# MCU_Power_Clock_Debug.net
KiCad netlist of a schematic drawn in Altium Designer
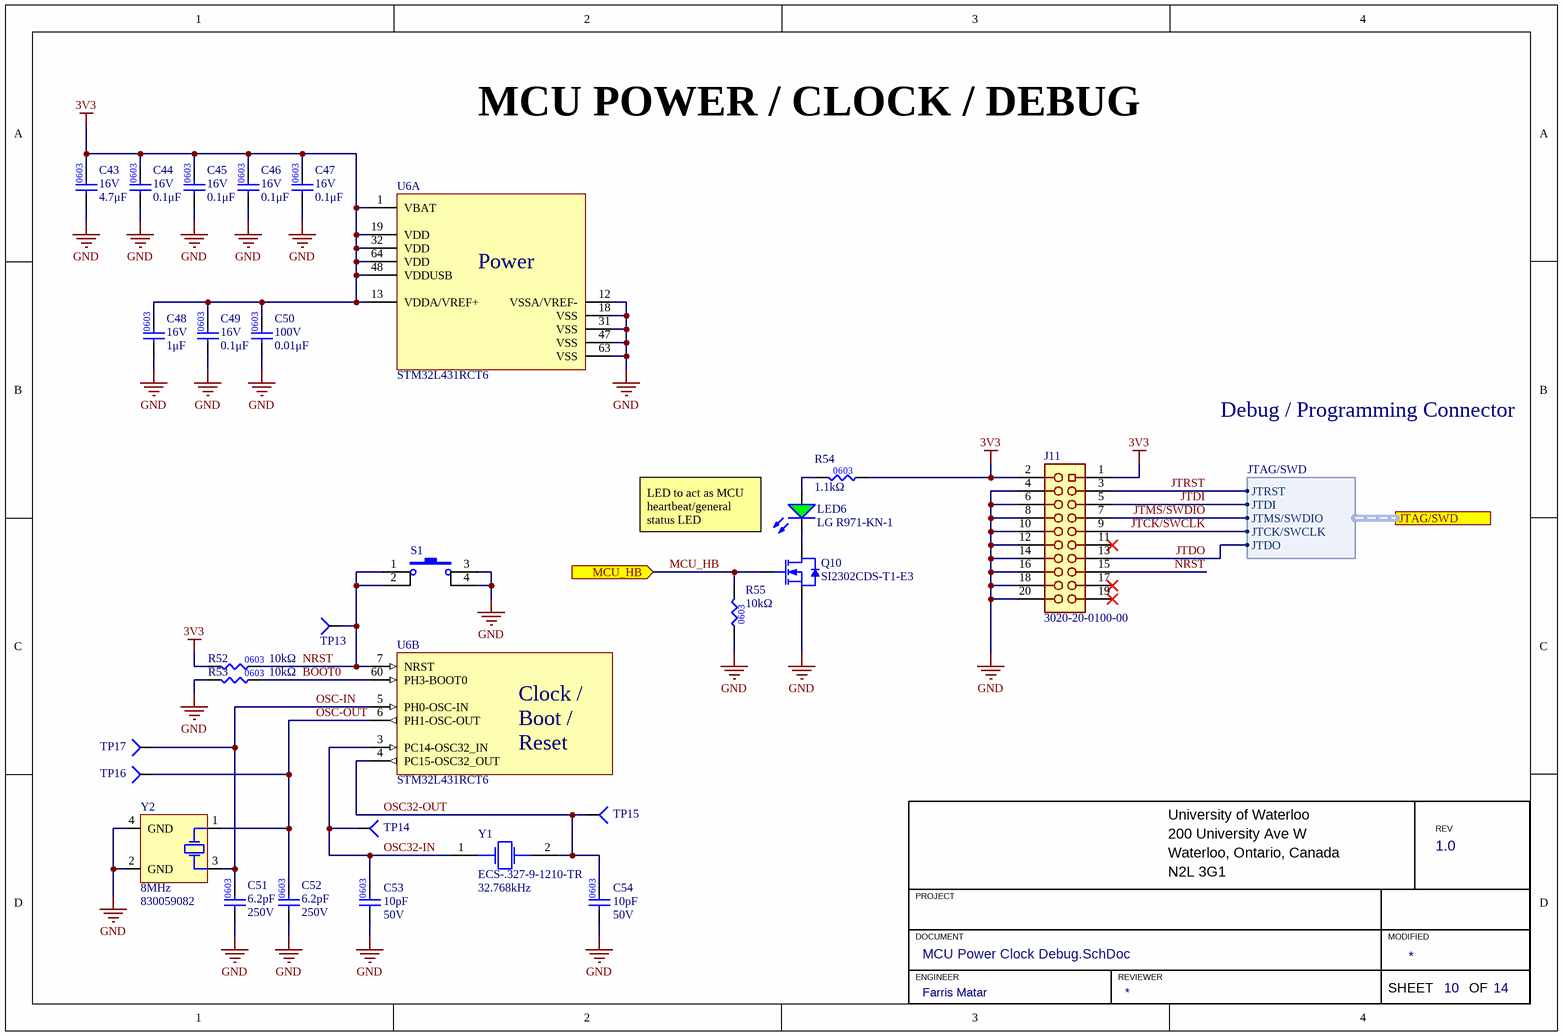
[diagram p0: MCU Power Clock Debug.SchDoc]

(export (version "E")
  (design (tool "Eeschema 10.0.6"))
  (components
    (comp (ref "C43")
      (value "4.7μF")
      (footprint "CAP0603")
      (description "CAP CER 4.7UF 16V X6S 0603")
      (fields (field (name "VOLTAGE RATING") "16V") (field (name "Comment") "CAP_4.7uF_16V_0603"))
      (libsource (lib "Personal_Schematic_Library_2022") (part "CAP_4.7uF_16V_0603"))
    )
    (comp (ref "C44")
      (value "0.1μF")
      (footprint "CAP0603")
      (description "CAP CER 0.1UF 16V X7R 0603")
      (fields (field (name "VOLTAGE RATING") "16V") (field (name "Comment") "CAP_0.1uF_16V_0603"))
      (libsource (lib "Personal_Schematic_Library_2022") (part "CAP_0.1uF_16V_0603"))
    )
    (comp (ref "C45")
      (value "0.1μF")
      (footprint "CAP0603")
      (description "CAP CER 0.1UF 16V X7R 0603")
      (fields (field (name "VOLTAGE RATING") "16V") (field (name "Comment") "CAP_0.1uF_16V_0603"))
      (libsource (lib "Personal_Schematic_Library_2022") (part "CAP_0.1uF_16V_0603"))
    )
    (comp (ref "C46")
      (value "0.1μF")
      (footprint "CAP0603")
      (description "CAP CER 0.1UF 16V X7R 0603")
      (fields (field (name "VOLTAGE RATING") "16V") (field (name "Comment") "CAP_0.1uF_16V_0603"))
      (libsource (lib "Personal_Schematic_Library_2022") (part "CAP_0.1uF_16V_0603"))
    )
    (comp (ref "C47")
      (value "0.1μF")
      (footprint "CAP0603")
      (description "CAP CER 0.1UF 16V X7R 0603")
      (fields (field (name "VOLTAGE RATING") "16V") (field (name "Comment") "CAP_0.1uF_16V_0603"))
      (libsource (lib "Personal_Schematic_Library_2022") (part "CAP_0.1uF_16V_0603"))
    )
    (comp (ref "C48")
      (value "1μF")
      (footprint "CAP0603")
      (description "CAP CER 1UF 16V X7R 0603")
      (fields (field (name "VOLTAGE RATING") "16V") (field (name "Comment") "CAP_1uF_16V_0603"))
      (libsource (lib "Personal_Schematic_Library_2022") (part "CAP_1uF_16V_0603"))
    )
    (comp (ref "C49")
      (value "0.1μF")
      (footprint "CAP0603")
      (description "CAP CER 0.1UF 16V X7R 0603")
      (fields (field (name "VOLTAGE RATING") "16V") (field (name "Comment") "CAP_0.1uF_16V_0603"))
      (libsource (lib "Personal_Schematic_Library_2022") (part "CAP_0.1uF_16V_0603"))
    )
    (comp (ref "C50")
      (value "0.01μF")
      (footprint "CAP0603")
      (description "CAP CER 0.01uF 100V X7R 0603")
      (fields (field (name "VOLTAGE RATING") "100V") (field (name "Comment") "CAP_0.01uF_100V_0603"))
      (libsource (lib "Personal_Schematic_Library_2022") (part "CAP_0.01uF_100V_0603"))
    )
    (comp (ref "C51")
      (value "6.2pF")
      (footprint "CAP0603")
      (description "HVCAP0603 COG 6.2PF .25PF 250V")
      (fields (field (name "VOLTAGE RATING") "250V") (field (name "Comment") "CAP_6.2pF_250V_0603"))
      (libsource (lib "Personal_Schematic_Library_2022") (part "CAP_6.2pF_250V_0603"))
    )
    (comp (ref "C52")
      (value "6.2pF")
      (footprint "CAP0603")
      (description "HVCAP0603 COG 6.2PF .25PF 250V")
      (fields (field (name "VOLTAGE RATING") "250V") (field (name "Comment") "CAP_6.2pF_250V_0603"))
      (libsource (lib "Personal_Schematic_Library_2022") (part "CAP_6.2pF_250V_0603"))
    )
    (comp (ref "C53")
      (value "10pF")
      (footprint "CAP0603")
      (description "CAP CER 10PF 50V X7R 0603")
      (fields (field (name "VOLTAGE RATING") "50V") (field (name "Comment") "CAP_10pF_50V_0603"))
      (libsource (lib "Personal_Schematic_Library_2022") (part "CAP_10pF_50V_0603"))
    )
    (comp (ref "C54")
      (value "10pF")
      (footprint "CAP0603")
      (description "CAP CER 10PF 50V X7R 0603")
      (fields (field (name "VOLTAGE RATING") "50V") (field (name "Comment") "CAP_10pF_50V_0603"))
      (libsource (lib "Personal_Schematic_Library_2022") (part "CAP_10pF_50V_0603"))
    )
    (comp (ref "J11")
      (value "3020-20-0100-00")
      (footprint "CNC_3020-20-0100-00")
      (description "CONN HEADER VERT 20POS 2.54MM")
      (libsource (lib "Personal_Schematic_Library_2022") (part "CON_10x2_HEADER"))
    )
    (comp (ref "LED6")
      (value "LED_GREEN")
      (footprint "LED_0805_GREEN")
      (description "LED GREEN DIFFUSED 0805 SMD")
      (fields (field (name "MANUFACTURER PART NUMBER 1") "LG R971-KN-1"))
      (libsource (lib "Personal_Schematic_Library_2022") (part "LED_GREEN"))
    )
    (comp (ref "Q10")
      (value "NMOS_20V_6A")
      (footprint "SOT23-3")
      (description "MOSFET N-CH 20V 2.6A SOT23-3")
      (fields (field (name "MANUFACTURER PART NUMBER 1") "SI2302CDS-T1-E3"))
      (libsource (lib "Personal_Schematic_Library_2022") (part "NMOS_20V_2.6A"))
    )
    (comp (ref "R52")
      (value "10kΩ")
      (footprint "RES0603")
      (description "RES 10K OHM 1% 1/8W 0603")
      (fields (field (name "Comment") "RES_10kΩ_0603_1%"))
      (libsource (lib "Personal_Schematic_Library_2022") (part "RES_10kΩ_0603_1%"))
    )
    (comp (ref "R53")
      (value "10kΩ")
      (footprint "RES0603")
      (description "RES 10K OHM 1% 1/8W 0603")
      (fields (field (name "Comment") "RES_10kΩ_0603_1%"))
      (libsource (lib "Personal_Schematic_Library_2022") (part "RES_10kΩ_0603_1%"))
    )
    (comp (ref "R54")
      (value "1.1kΩ")
      (footprint "RES0603")
      (description "RES 1.1K OHM 1% 1/10W 0603")
      (fields (field (name "Comment") "RES_1.1kΩ_0603_1%"))
      (libsource (lib "Personal_Schematic_Library_2022") (part "RES_1.1kΩ_0603_1%"))
    )
    (comp (ref "R55")
      (value "10kΩ")
      (footprint "RES0603")
      (description "RES 10K OHM 1% 1/8W 0603")
      (fields (field (name "Comment") "RES_10kΩ_0603_1%"))
      (libsource (lib "Personal_Schematic_Library_2022") (part "RES_10kΩ_0603_1%"))
    )
    (comp (ref "S1")
      (value "SW_SPST_NO_4.5x4.5")
      (footprint "SPST_PUSHBUTTON_TL3305AF260QG")
      (description "SWITCH TACTILE SPST-NO 50MA 12V")
      (libsource (lib "Personal_Schematic_Library_2022") (part "SW_SPST_NO_4.5x4.5"))
    )
    (comp (ref "TP13")
      (value "TESTPOINT_1MM_CIRCLE")
      (footprint "TESTPOINT_CIRCLE_1MM")
      (description "TESTPOINT 1MM CIRCLE")
      (libsource (lib "Personal_Schematic_Library_2022") (part "TESTPOINT_1MM_CIRCLE"))
    )
    (comp (ref "TP14")
      (value "TESTPOINT_1MM_CIRCLE")
      (footprint "TESTPOINT_CIRCLE_1MM")
      (description "TESTPOINT 1MM CIRCLE")
      (libsource (lib "Personal_Schematic_Library_2022") (part "TESTPOINT_1MM_CIRCLE"))
    )
    (comp (ref "TP15")
      (value "TESTPOINT_1MM_CIRCLE")
      (footprint "TESTPOINT_CIRCLE_1MM")
      (description "TESTPOINT 1MM CIRCLE")
      (libsource (lib "Personal_Schematic_Library_2022") (part "TESTPOINT_1MM_CIRCLE"))
    )
    (comp (ref "TP16")
      (value "TESTPOINT_1MM_CIRCLE")
      (footprint "TESTPOINT_CIRCLE_1MM")
      (description "TESTPOINT 1MM CIRCLE")
      (libsource (lib "Personal_Schematic_Library_2022") (part "TESTPOINT_1MM_CIRCLE"))
    )
    (comp (ref "TP17")
      (value "TESTPOINT_1MM_CIRCLE")
      (footprint "TESTPOINT_CIRCLE_1MM")
      (description "TESTPOINT 1MM CIRCLE")
      (libsource (lib "Personal_Schematic_Library_2022") (part "TESTPOINT_1MM_CIRCLE"))
    )
    (comp (ref "U6")
      (value "STM32L431RCT6")
      (footprint "STM_LQFP64")
      (description "IC MCU 32BIT 256KB FLASH 64LQFP")
      (libsource (lib "Personal_Schematic_Library_2022") (part "STM32L431RCT6"))
    )
    (comp (ref "Y1")
      (value "CRYSTAL_32.768KHZ")
      (footprint "OSC_ECS-327TR-2")
      (description "CRYSTAL 32.7680KHZ 9PF SMD")
      (fields
        (field (name "FREQUENCY") "32.768kHz")
        (field (name "MANUFACTURER PART NUMBER 1") "ECS-.327-9-1210-TR")
      )
      (libsource (lib "Personal_Schematic_Library_2022") (part "CRYSTAL_32.768KHZ"))
    )
    (comp (ref "Y2")
      (value "CRYSTAL_25MHZ")
      (footprint "XTAL_WURTH_830059082")
      (description "WE-XTAL QUARTZ CRYSTAL 8.0 MHZ;")
      (fields (field (name "FREQUENCY") "8MHz") (field (name "MANUFACTURER PART NUMBER 1") "830059082"))
      (libsource (lib "Personal_Schematic_Library_2022") (part "CRYSTAL_8MHZ_8PF"))
    )
  )
  (nets
    (net (code "2") (name "/BOOT0") (class "Default")
      (node (ref "R53") (pin "2") (pinfunction "2_2") (pintype "passive"))
      (node (ref "U6") (pin "60") (pinfunction "PH3-BOOT0_60") (pintype "input"))
    )
    (net (code "3") (name "/JTCK{slash}SWCLK") (class "Default")
      (node (ref "J11") (pin "9") (pinfunction "9_9") (pintype "passive"))
    )
    (net (code "4") (name "/JTDI") (class "Default")
      (node (ref "J11") (pin "5") (pinfunction "5_5") (pintype "passive"))
    )
    (net (code "5") (name "/JTDO") (class "Default")
      (node (ref "J11") (pin "13") (pinfunction "13_13") (pintype "passive"))
    )
    (net (code "6") (name "/JTMS{slash}SWDIO") (class "Default")
      (node (ref "J11") (pin "7") (pinfunction "7_7") (pintype "passive"))
    )
    (net (code "7") (name "/JTRST") (class "Default")
      (node (ref "J11") (pin "3") (pinfunction "3_3") (pintype "passive"))
    )
    (net (code "8") (name "/MCU_HB") (class "Default")
      (node (ref "Q10") (pin "1") (pinfunction "GATE_1") (pintype "passive"))
      (node (ref "R55") (pin "2") (pinfunction "2_2") (pintype "passive"))
    )
    (net (code "9") (name "/NRST") (class "Default")
      (node (ref "J11") (pin "15") (pinfunction "15_15") (pintype "passive"))
      (node (ref "R52") (pin "2") (pinfunction "2_2") (pintype "passive"))
      (node (ref "S1") (pin "1") (pinfunction "1_1") (pintype "passive"))
      (node (ref "S1") (pin "2") (pinfunction "2_2") (pintype "passive"))
      (node (ref "TP13") (pin "1") (pinfunction "=value_1") (pintype "passive"))
      (node (ref "U6") (pin "7") (pinfunction "NRST_7") (pintype "input"))
    )
    (net (code "10") (name "/OSC-IN") (class "Default")
      (node (ref "C51") (pin "2") (pinfunction "2_2") (pintype "passive"))
      (node (ref "TP17") (pin "1") (pinfunction "=value_1") (pintype "passive"))
      (node (ref "U6") (pin "5") (pinfunction "PH0-OSC-IN_5") (pintype "input"))
      (node (ref "Y2") (pin "3") (pinfunction "HOT_3") (pintype "passive"))
    )
    (net (code "11") (name "/OSC-OUT") (class "Default")
      (node (ref "C52") (pin "2") (pinfunction "2_2") (pintype "passive"))
      (node (ref "TP16") (pin "1") (pinfunction "=value_1") (pintype "passive"))
      (node (ref "U6") (pin "6") (pinfunction "PH1-OSC-OUT_6") (pintype "output"))
      (node (ref "Y2") (pin "1") (pinfunction "HOT_1") (pintype "passive"))
    )
    (net (code "12") (name "/OSC32-IN") (class "Default")
      (node (ref "C53") (pin "2") (pinfunction "2_2") (pintype "passive"))
      (node (ref "TP14") (pin "1") (pinfunction "=value_1") (pintype "passive"))
      (node (ref "U6") (pin "3") (pinfunction "PC14-OSC32_IN_3") (pintype "input"))
      (node (ref "Y1") (pin "1") (pinfunction "1_1") (pintype "passive"))
    )
    (net (code "13") (name "/OSC32-OUT") (class "Default")
      (node (ref "C54") (pin "2") (pinfunction "2_2") (pintype "passive"))
      (node (ref "TP15") (pin "1") (pinfunction "=value_1") (pintype "passive"))
      (node (ref "U6") (pin "4") (pinfunction "PC15-OSC32_OUT_4") (pintype "output"))
      (node (ref "Y1") (pin "2") (pinfunction "2_2") (pintype "passive"))
    )
    (net (code "15") (name "3V3") (class "Default")
      (node (ref "C43") (pin "2") (pinfunction "2_2") (pintype "passive"))
      (node (ref "C44") (pin "2") (pinfunction "2_2") (pintype "passive"))
      (node (ref "C45") (pin "2") (pinfunction "2_2") (pintype "passive"))
      (node (ref "C46") (pin "2") (pinfunction "2_2") (pintype "passive"))
      (node (ref "C47") (pin "2") (pinfunction "2_2") (pintype "passive"))
      (node (ref "C48") (pin "2") (pinfunction "2_2") (pintype "passive"))
      (node (ref "C49") (pin "2") (pinfunction "2_2") (pintype "passive"))
      (node (ref "C50") (pin "2") (pinfunction "2_2") (pintype "passive"))
      (node (ref "J11") (pin "1") (pinfunction "1_1") (pintype "passive"))
      (node (ref "J11") (pin "2") (pinfunction "2_2") (pintype "passive"))
      (node (ref "R52") (pin "1") (pinfunction "1_1") (pintype "passive"))
      (node (ref "R54") (pin "1") (pinfunction "1_1") (pintype "passive"))
      (node (ref "U6") (pin "1") (pinfunction "VBAT_1") (pintype "power_in"))
      (node (ref "U6") (pin "13") (pinfunction "VDDA/VREF+_13") (pintype "power_in"))
      (node (ref "U6") (pin "19") (pinfunction "VDD_19") (pintype "power_in"))
      (node (ref "U6") (pin "32") (pinfunction "VDD_32") (pintype "power_in"))
      (node (ref "U6") (pin "48") (pinfunction "VDDUSB_48") (pintype "power_in"))
      (node (ref "U6") (pin "64") (pinfunction "VDD_64") (pintype "power_in"))
    )
    (net (code "16") (name "GND") (class "Default")
      (node (ref "C43") (pin "1") (pinfunction "1_1") (pintype "passive"))
      (node (ref "C44") (pin "1") (pinfunction "1_1") (pintype "passive"))
      (node (ref "C45") (pin "1") (pinfunction "1_1") (pintype "passive"))
      (node (ref "C46") (pin "1") (pinfunction "1_1") (pintype "passive"))
      (node (ref "C47") (pin "1") (pinfunction "1_1") (pintype "passive"))
      (node (ref "C48") (pin "1") (pinfunction "1_1") (pintype "passive"))
      (node (ref "C49") (pin "1") (pinfunction "1_1") (pintype "passive"))
      (node (ref "C50") (pin "1") (pinfunction "1_1") (pintype "passive"))
      (node (ref "C51") (pin "1") (pinfunction "1_1") (pintype "passive"))
      (node (ref "C52") (pin "1") (pinfunction "1_1") (pintype "passive"))
      (node (ref "C53") (pin "1") (pinfunction "1_1") (pintype "passive"))
      (node (ref "C54") (pin "1") (pinfunction "1_1") (pintype "passive"))
      (node (ref "J11") (pin "10") (pinfunction "10_10") (pintype "passive"))
      (node (ref "J11") (pin "12") (pinfunction "12_12") (pintype "passive"))
      (node (ref "J11") (pin "14") (pinfunction "14_14") (pintype "passive"))
      (node (ref "J11") (pin "16") (pinfunction "16_16") (pintype "passive"))
      (node (ref "J11") (pin "18") (pinfunction "18_18") (pintype "passive"))
      (node (ref "J11") (pin "20") (pinfunction "20_20") (pintype "passive"))
      (node (ref "J11") (pin "4") (pinfunction "4_4") (pintype "passive"))
      (node (ref "J11") (pin "6") (pinfunction "6_6") (pintype "passive"))
      (node (ref "J11") (pin "8") (pinfunction "8_8") (pintype "passive"))
      (node (ref "Q10") (pin "2") (pinfunction "SOURCE_2") (pintype "passive"))
      (node (ref "R53") (pin "1") (pinfunction "1_1") (pintype "passive"))
      (node (ref "R55") (pin "1") (pinfunction "1_1") (pintype "passive"))
      (node (ref "S1") (pin "3") (pinfunction "3_3") (pintype "passive"))
      (node (ref "S1") (pin "4") (pinfunction "4_4") (pintype "passive"))
      (node (ref "U6") (pin "12") (pinfunction "VSSA/VREF-_12") (pintype "power_in"))
      (node (ref "U6") (pin "18") (pinfunction "VSS_18") (pintype "power_in"))
      (node (ref "U6") (pin "31") (pinfunction "VSS_31") (pintype "power_in"))
      (node (ref "U6") (pin "47") (pinfunction "VSS_47") (pintype "power_in"))
      (node (ref "U6") (pin "63") (pinfunction "VSS_63") (pintype "power_in"))
      (node (ref "Y2") (pin "2") (pinfunction "GND_2") (pintype "power_in"))
      (node (ref "Y2") (pin "4") (pinfunction "GND_4") (pintype "power_in"))
    )
    (net (code "17") (name "Net-(LED6-A)") (class "Default")
      (node (ref "LED6") (pin "1") (pinfunction "A_1") (pintype "passive"))
      (node (ref "R54") (pin "2") (pinfunction "2_2") (pintype "passive"))
    )
    (net (code "18") (name "Net-(LED6-K)") (class "Default")
      (node (ref "LED6") (pin "2") (pinfunction "K_2") (pintype "passive"))
      (node (ref "Q10") (pin "3") (pinfunction "DRAIN_3") (pintype "passive"))
    )
    (net (code "19") (name "unconnected-(J11-Pad11)") (class "Default")
      (node (ref "J11") (pin "11") (pinfunction "11_11") (pintype "passive+no_connect"))
    )
    (net (code "20") (name "unconnected-(J11-Pad17)") (class "Default")
      (node (ref "J11") (pin "17") (pinfunction "17_17") (pintype "passive+no_connect"))
    )
    (net (code "21") (name "unconnected-(J11-Pad19)") (class "Default")
      (node (ref "J11") (pin "19") (pinfunction "19_19") (pintype "passive+no_connect"))
    )
  )
)
